# ADC.net
KiCad netlist of a schematic drawn in Altium Designer
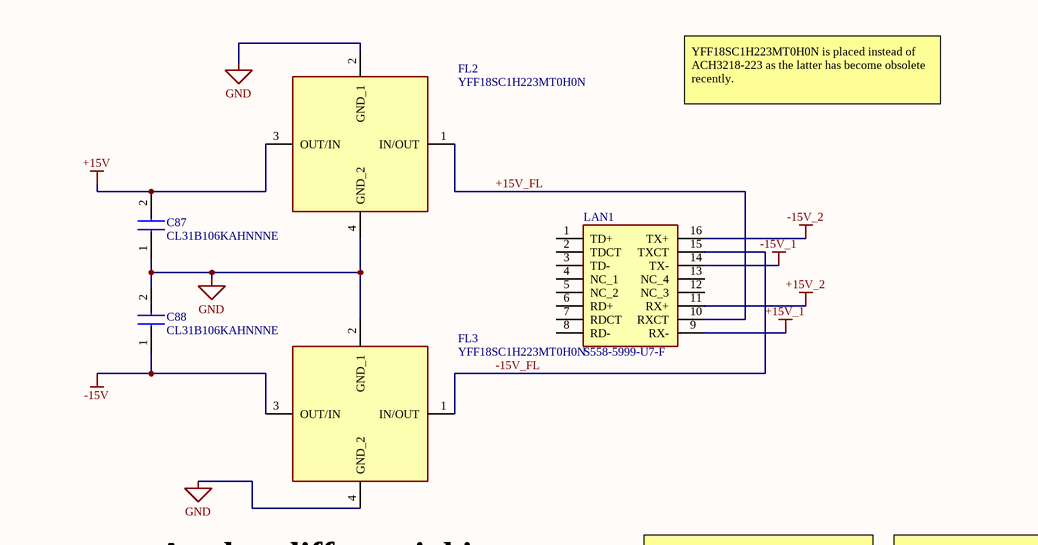
[diagram p0: ADC.SchDoc, top left]
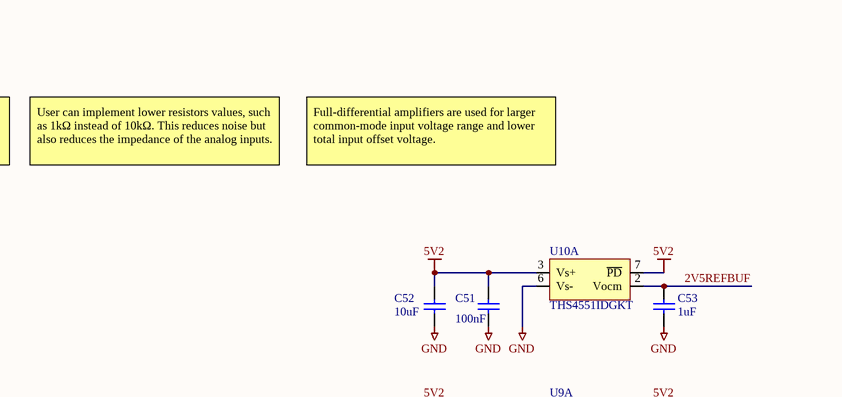
[diagram p1: ADC.SchDoc, top right]
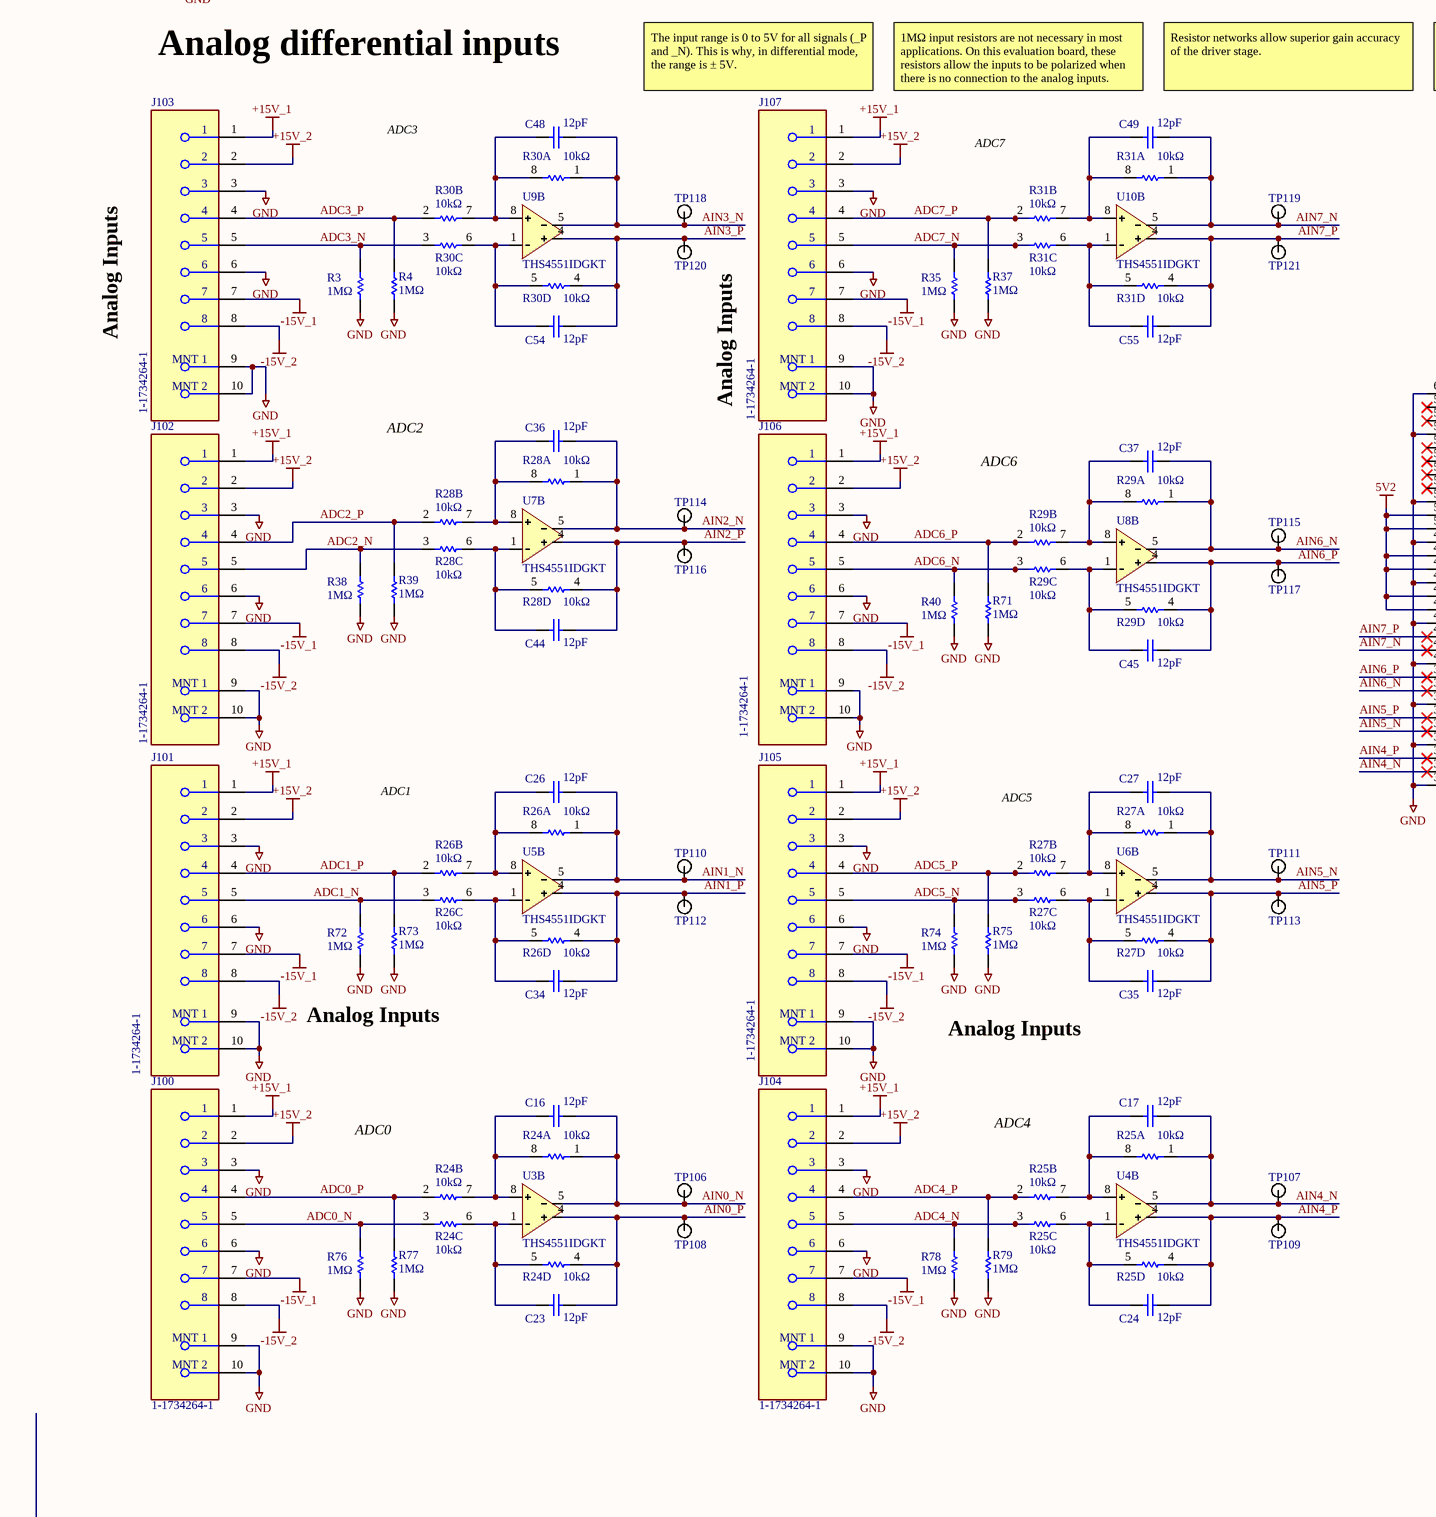
[diagram p2: ADC.SchDoc, bottom left]
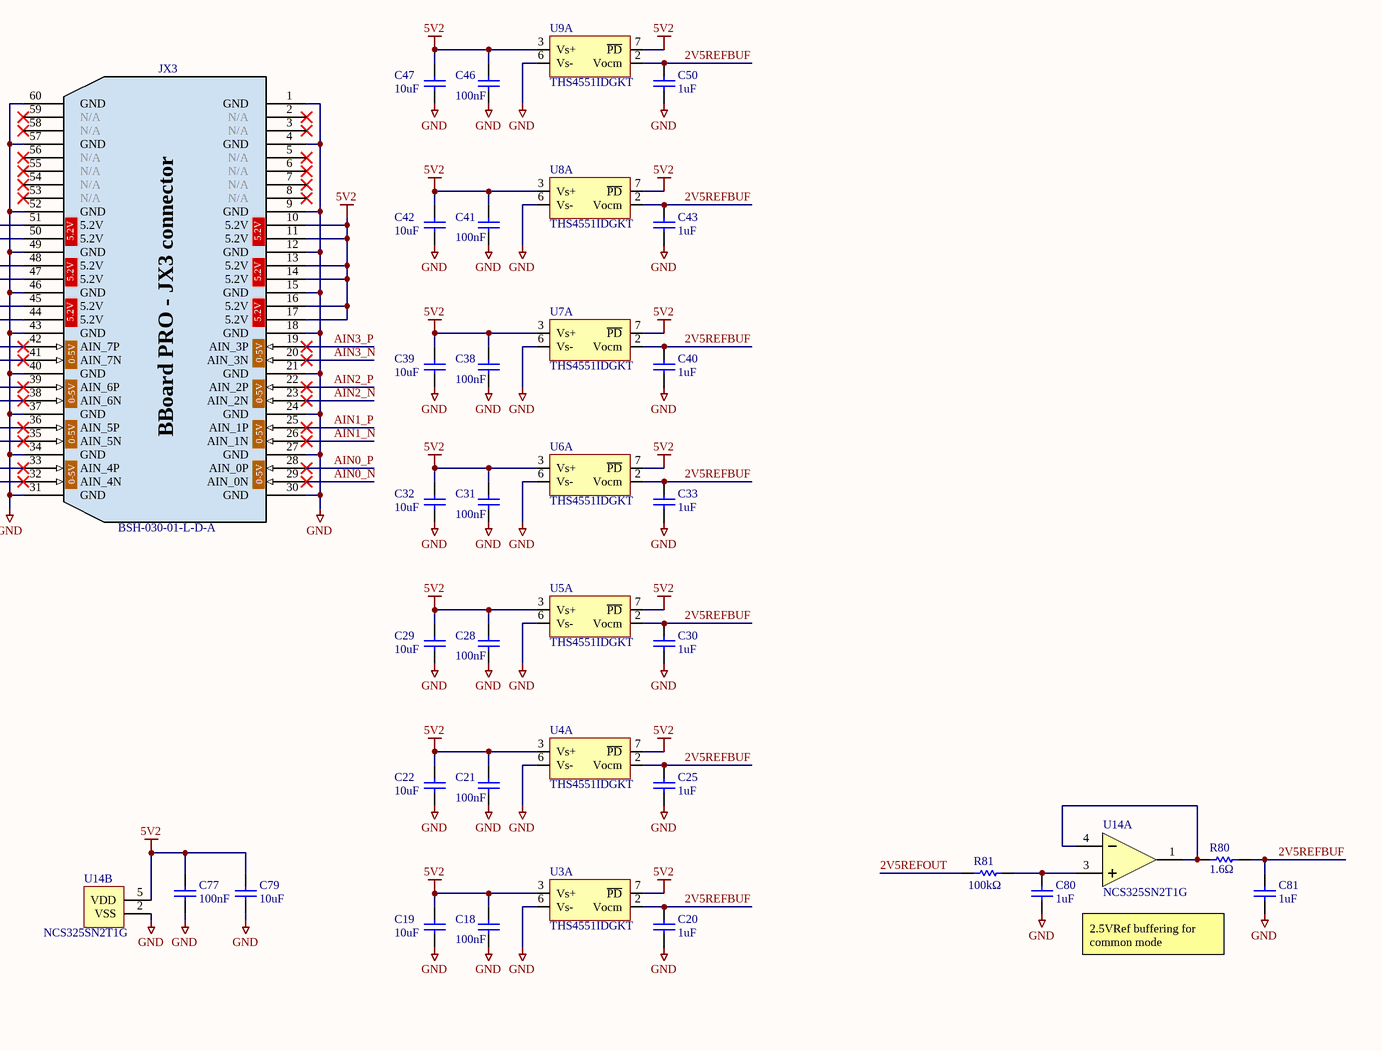
[diagram p3: ADC.SchDoc, bottom right]

(export (version "E")
  (design (tool "Eeschema 10.0.6"))
  (components
    (comp (ref "C16")
      (value "12pF")
      (footprint "CAPC1005L(0402)")
      (description "CAP CER 12PF 50V C0G 0402 5% (Generic Imperix Component)")
      (fields (field (name "TOLERANCE") "5%") (field (name "Comment") "CAP-12PF-50V-C0G-0402-5%"))
      (libsource (lib "CB3-ECB") (part "Capacitor non-polarized"))
    )
    (comp (ref "C17")
      (value "12pF")
      (footprint "CAPC1005L(0402)")
      (description "CAP CER 12PF 50V C0G 0402 5% (Generic Imperix Component)")
      (fields (field (name "TOLERANCE") "5%") (field (name "Comment") "CAP-12PF-50V-C0G-0402-5%"))
      (libsource (lib "CB3-ECB") (part "Capacitor non-polarized"))
    )
    (comp (ref "C18")
      (value "100nF")
      (footprint "CAPC1005L(0402)")
      (description "CAP CER 100NF 25V X7R 0402 10% (Generic Imperix Component)")
      (fields (field (name "TOLERANCE") "10%") (field (name "Comment") "CAP-100NF-25V-X7R-0402-10%"))
      (libsource (lib "CB3-ECB") (part "Capacitor non-polarized"))
    )
    (comp (ref "C19")
      (value "10uF")
      (footprint "CAPC1608L(0603)")
      (description "CAP CER 10UF 10V X5R 0603 10% (Generic Imperix Component)")
      (fields (field (name "TOLERANCE") "10%") (field (name "Comment") "CAP-10UF-10V-X5R-0603-10%"))
      (libsource (lib "CB3-ECB") (part "Capacitor non-polarized"))
    )
    (comp (ref "C20")
      (value "1uF")
      (footprint "CAPC1005L(0402)")
      (description "CAP CER 1UF 6.3V X5R 0402 5% (Generic Imperix Component)")
      (fields (field (name "TOLERANCE") "5%") (field (name "Comment") "CAP-1UF-6.3V-X5R-0402-5%"))
      (libsource (lib "CB3-ECB") (part "Capacitor non-polarized"))
    )
    (comp (ref "C21")
      (value "100nF")
      (footprint "CAPC1005L(0402)")
      (description "CAP CER 100NF 25V X7R 0402 10% (Generic Imperix Component)")
      (fields (field (name "TOLERANCE") "10%") (field (name "Comment") "CAP-100NF-25V-X7R-0402-10%"))
      (libsource (lib "CB3-ECB") (part "Capacitor non-polarized"))
    )
    (comp (ref "C22")
      (value "10uF")
      (footprint "CAPC1608L(0603)")
      (description "CAP CER 10UF 10V X5R 0603 10% (Generic Imperix Component)")
      (fields (field (name "TOLERANCE") "10%") (field (name "Comment") "CAP-10UF-10V-X5R-0603-10%"))
      (libsource (lib "CB3-ECB") (part "Capacitor non-polarized"))
    )
    (comp (ref "C23")
      (value "12pF")
      (footprint "CAPC1005L(0402)")
      (description "CAP CER 12PF 50V C0G 0402 5% (Generic Imperix Component)")
      (fields (field (name "TOLERANCE") "5%") (field (name "Comment") "CAP-12PF-50V-C0G-0402-5%"))
      (libsource (lib "CB3-ECB") (part "Capacitor non-polarized"))
    )
    (comp (ref "C24")
      (value "12pF")
      (footprint "CAPC1005L(0402)")
      (description "CAP CER 12PF 50V C0G 0402 5% (Generic Imperix Component)")
      (fields (field (name "TOLERANCE") "5%") (field (name "Comment") "CAP-12PF-50V-C0G-0402-5%"))
      (libsource (lib "CB3-ECB") (part "Capacitor non-polarized"))
    )
    (comp (ref "C25")
      (value "1uF")
      (footprint "CAPC1005L(0402)")
      (description "CAP CER 1UF 6.3V X5R 0402 5% (Generic Imperix Component)")
      (fields (field (name "TOLERANCE") "5%") (field (name "Comment") "CAP-1UF-6.3V-X5R-0402-5%"))
      (libsource (lib "CB3-ECB") (part "Capacitor non-polarized"))
    )
    (comp (ref "C26")
      (value "12pF")
      (footprint "CAPC1005L(0402)")
      (description "CAP CER 12PF 50V C0G 0402 5% (Generic Imperix Component)")
      (fields (field (name "TOLERANCE") "5%") (field (name "Comment") "CAP-12PF-50V-C0G-0402-5%"))
      (libsource (lib "CB3-ECB") (part "Capacitor non-polarized"))
    )
    (comp (ref "C27")
      (value "12pF")
      (footprint "CAPC1005L(0402)")
      (description "CAP CER 12PF 50V C0G 0402 5% (Generic Imperix Component)")
      (fields (field (name "TOLERANCE") "5%") (field (name "Comment") "CAP-12PF-50V-C0G-0402-5%"))
      (libsource (lib "CB3-ECB") (part "Capacitor non-polarized"))
    )
    (comp (ref "C28")
      (value "100nF")
      (footprint "CAPC1005L(0402)")
      (description "CAP CER 100NF 25V X7R 0402 10% (Generic Imperix Component)")
      (fields (field (name "TOLERANCE") "10%") (field (name "Comment") "CAP-100NF-25V-X7R-0402-10%"))
      (libsource (lib "CB3-ECB") (part "Capacitor non-polarized"))
    )
    (comp (ref "C29")
      (value "10uF")
      (footprint "CAPC1608L(0603)")
      (description "CAP CER 10UF 10V X5R 0603 10% (Generic Imperix Component)")
      (fields (field (name "TOLERANCE") "10%") (field (name "Comment") "CAP-10UF-10V-X5R-0603-10%"))
      (libsource (lib "CB3-ECB") (part "Capacitor non-polarized"))
    )
    (comp (ref "C30")
      (value "1uF")
      (footprint "CAPC1005L(0402)")
      (description "CAP CER 1UF 6.3V X5R 0402 5% (Generic Imperix Component)")
      (fields (field (name "TOLERANCE") "5%") (field (name "Comment") "CAP-1UF-6.3V-X5R-0402-5%"))
      (libsource (lib "CB3-ECB") (part "Capacitor non-polarized"))
    )
    (comp (ref "C31")
      (value "100nF")
      (footprint "CAPC1005L(0402)")
      (description "CAP CER 100NF 25V X7R 0402 10% (Generic Imperix Component)")
      (fields (field (name "TOLERANCE") "10%") (field (name "Comment") "CAP-100NF-25V-X7R-0402-10%"))
      (libsource (lib "CB3-ECB") (part "Capacitor non-polarized"))
    )
    (comp (ref "C32")
      (value "10uF")
      (footprint "CAPC1608L(0603)")
      (description "CAP CER 10UF 10V X5R 0603 10% (Generic Imperix Component)")
      (fields (field (name "TOLERANCE") "10%") (field (name "Comment") "CAP-10UF-10V-X5R-0603-10%"))
      (libsource (lib "CB3-ECB") (part "Capacitor non-polarized"))
    )
    (comp (ref "C33")
      (value "1uF")
      (footprint "CAPC1005L(0402)")
      (description "CAP CER 1UF 6.3V X5R 0402 5% (Generic Imperix Component)")
      (fields (field (name "TOLERANCE") "5%") (field (name "Comment") "CAP-1UF-6.3V-X5R-0402-5%"))
      (libsource (lib "CB3-ECB") (part "Capacitor non-polarized"))
    )
    (comp (ref "C34")
      (value "12pF")
      (footprint "CAPC1005L(0402)")
      (description "CAP CER 12PF 50V C0G 0402 5% (Generic Imperix Component)")
      (fields (field (name "TOLERANCE") "5%") (field (name "Comment") "CAP-12PF-50V-C0G-0402-5%"))
      (libsource (lib "CB3-ECB") (part "Capacitor non-polarized"))
    )
    (comp (ref "C35")
      (value "12pF")
      (footprint "CAPC1005L(0402)")
      (description "CAP CER 12PF 50V C0G 0402 5% (Generic Imperix Component)")
      (fields (field (name "TOLERANCE") "5%") (field (name "Comment") "CAP-12PF-50V-C0G-0402-5%"))
      (libsource (lib "CB3-ECB") (part "Capacitor non-polarized"))
    )
    (comp (ref "C36")
      (value "12pF")
      (footprint "CAPC1005L(0402)")
      (description "CAP CER 12PF 50V C0G 0402 5% (Generic Imperix Component)")
      (fields (field (name "TOLERANCE") "5%") (field (name "Comment") "CAP-12PF-50V-C0G-0402-5%"))
      (libsource (lib "CB3-ECB") (part "Capacitor non-polarized"))
    )
    (comp (ref "C37")
      (value "12pF")
      (footprint "CAPC1005L(0402)")
      (description "CAP CER 12PF 50V C0G 0402 5% (Generic Imperix Component)")
      (fields (field (name "TOLERANCE") "5%") (field (name "Comment") "CAP-12PF-50V-C0G-0402-5%"))
      (libsource (lib "CB3-ECB") (part "Capacitor non-polarized"))
    )
    (comp (ref "C38")
      (value "100nF")
      (footprint "CAPC1005L(0402)")
      (description "CAP CER 100NF 25V X7R 0402 10% (Generic Imperix Component)")
      (fields (field (name "TOLERANCE") "10%") (field (name "Comment") "CAP-100NF-25V-X7R-0402-10%"))
      (libsource (lib "CB3-ECB") (part "Capacitor non-polarized"))
    )
    (comp (ref "C39")
      (value "10uF")
      (footprint "CAPC1608L(0603)")
      (description "CAP CER 10UF 10V X5R 0603 10% (Generic Imperix Component)")
      (fields (field (name "TOLERANCE") "10%") (field (name "Comment") "CAP-10UF-10V-X5R-0603-10%"))
      (libsource (lib "CB3-ECB") (part "Capacitor non-polarized"))
    )
    (comp (ref "C40")
      (value "1uF")
      (footprint "CAPC1005L(0402)")
      (description "CAP CER 1UF 6.3V X5R 0402 5% (Generic Imperix Component)")
      (fields (field (name "TOLERANCE") "5%") (field (name "Comment") "CAP-1UF-6.3V-X5R-0402-5%"))
      (libsource (lib "CB3-ECB") (part "Capacitor non-polarized"))
    )
    (comp (ref "C41")
      (value "100nF")
      (footprint "CAPC1005L(0402)")
      (description "CAP CER 100NF 25V X7R 0402 10% (Generic Imperix Component)")
      (fields (field (name "TOLERANCE") "10%") (field (name "Comment") "CAP-100NF-25V-X7R-0402-10%"))
      (libsource (lib "CB3-ECB") (part "Capacitor non-polarized"))
    )
    (comp (ref "C42")
      (value "10uF")
      (footprint "CAPC1608L(0603)")
      (description "CAP CER 10UF 10V X5R 0603 10% (Generic Imperix Component)")
      (fields (field (name "TOLERANCE") "10%") (field (name "Comment") "CAP-10UF-10V-X5R-0603-10%"))
      (libsource (lib "CB3-ECB") (part "Capacitor non-polarized"))
    )
    (comp (ref "C43")
      (value "1uF")
      (footprint "CAPC1005L(0402)")
      (description "CAP CER 1UF 6.3V X5R 0402 5% (Generic Imperix Component)")
      (fields (field (name "TOLERANCE") "5%") (field (name "Comment") "CAP-1UF-6.3V-X5R-0402-5%"))
      (libsource (lib "CB3-ECB") (part "Capacitor non-polarized"))
    )
    (comp (ref "C44")
      (value "12pF")
      (footprint "CAPC1005L(0402)")
      (description "CAP CER 12PF 50V C0G 0402 5% (Generic Imperix Component)")
      (fields (field (name "TOLERANCE") "5%") (field (name "Comment") "CAP-12PF-50V-C0G-0402-5%"))
      (libsource (lib "CB3-ECB") (part "Capacitor non-polarized"))
    )
    (comp (ref "C45")
      (value "12pF")
      (footprint "CAPC1005L(0402)")
      (description "CAP CER 12PF 50V C0G 0402 5% (Generic Imperix Component)")
      (fields (field (name "TOLERANCE") "5%") (field (name "Comment") "CAP-12PF-50V-C0G-0402-5%"))
      (libsource (lib "CB3-ECB") (part "Capacitor non-polarized"))
    )
    (comp (ref "C46")
      (value "100nF")
      (footprint "CAPC1005L(0402)")
      (description "CAP CER 100NF 25V X7R 0402 10% (Generic Imperix Component)")
      (fields (field (name "TOLERANCE") "10%") (field (name "Comment") "CAP-100NF-25V-X7R-0402-10%"))
      (libsource (lib "CB3-ECB") (part "Capacitor non-polarized"))
    )
    (comp (ref "C47")
      (value "10uF")
      (footprint "CAPC1608L(0603)")
      (description "CAP CER 10UF 10V X5R 0603 10% (Generic Imperix Component)")
      (fields (field (name "TOLERANCE") "10%") (field (name "Comment") "CAP-10UF-10V-X5R-0603-10%"))
      (libsource (lib "CB3-ECB") (part "Capacitor non-polarized"))
    )
    (comp (ref "C48")
      (value "12pF")
      (footprint "CAPC1005L(0402)")
      (description "CAP CER 12PF 50V C0G 0402 5% (Generic Imperix Component)")
      (fields (field (name "TOLERANCE") "5%") (field (name "Comment") "CAP-12PF-50V-C0G-0402-5%"))
      (libsource (lib "CB3-ECB") (part "Capacitor non-polarized"))
    )
    (comp (ref "C49")
      (value "12pF")
      (footprint "CAPC1005L(0402)")
      (description "CAP CER 12PF 50V C0G 0402 5% (Generic Imperix Component)")
      (fields (field (name "TOLERANCE") "5%") (field (name "Comment") "CAP-12PF-50V-C0G-0402-5%"))
      (libsource (lib "CB3-ECB") (part "Capacitor non-polarized"))
    )
    (comp (ref "C50")
      (value "1uF")
      (footprint "CAPC1005L(0402)")
      (description "CAP CER 1UF 6.3V X5R 0402 5% (Generic Imperix Component)")
      (fields (field (name "TOLERANCE") "5%") (field (name "Comment") "CAP-1UF-6.3V-X5R-0402-5%"))
      (libsource (lib "CB3-ECB") (part "Capacitor non-polarized"))
    )
    (comp (ref "C51")
      (value "100nF")
      (footprint "CAPC1005L(0402)")
      (description "CAP CER 100NF 25V X7R 0402 10% (Generic Imperix Component)")
      (fields (field (name "TOLERANCE") "10%") (field (name "Comment") "CAP-100NF-25V-X7R-0402-10%"))
      (libsource (lib "CB3-ECB") (part "Capacitor non-polarized"))
    )
    (comp (ref "C52")
      (value "10uF")
      (footprint "CAPC1608L(0603)")
      (description "CAP CER 10UF 10V X5R 0603 10% (Generic Imperix Component)")
      (fields (field (name "TOLERANCE") "10%") (field (name "Comment") "CAP-10UF-10V-X5R-0603-10%"))
      (libsource (lib "CB3-ECB") (part "Capacitor non-polarized"))
    )
    (comp (ref "C53")
      (value "1uF")
      (footprint "CAPC1005L(0402)")
      (description "CAP CER 1UF 6.3V X5R 0402 5% (Generic Imperix Component)")
      (fields (field (name "TOLERANCE") "5%") (field (name "Comment") "CAP-1UF-6.3V-X5R-0402-5%"))
      (libsource (lib "CB3-ECB") (part "Capacitor non-polarized"))
    )
    (comp (ref "C54")
      (value "12pF")
      (footprint "CAPC1005L(0402)")
      (description "CAP CER 12PF 50V C0G 0402 5% (Generic Imperix Component)")
      (fields (field (name "TOLERANCE") "5%") (field (name "Comment") "CAP-12PF-50V-C0G-0402-5%"))
      (libsource (lib "CB3-ECB") (part "Capacitor non-polarized"))
    )
    (comp (ref "C55")
      (value "12pF")
      (footprint "CAPC1005L(0402)")
      (description "CAP CER 12PF 50V C0G 0402 5% (Generic Imperix Component)")
      (fields (field (name "TOLERANCE") "5%") (field (name "Comment") "CAP-12PF-50V-C0G-0402-5%"))
      (libsource (lib "CB3-ECB") (part "Capacitor non-polarized"))
    )
    (comp (ref "C77")
      (value "100nF")
      (footprint "CAPC1005L(0402)")
      (description "CAP CER 100NF 25V X7R 0402 10% (Generic Imperix Component)")
      (fields (field (name "TOLERANCE") "10%") (field (name "Comment") "CAP-100NF-25V-X7R-0402-10%"))
      (libsource (lib "CB3-ECB") (part "Capacitor non-polarized"))
    )
    (comp (ref "C79")
      (value "10uF")
      (footprint "CAPC1608L(0603)")
      (description "CAP CER 10UF 10V X5R 0603 10% (Generic Imperix Component)")
      (fields (field (name "TOLERANCE") "10%") (field (name "Comment") "CAP-10UF-10V-X5R-0603-10%"))
      (libsource (lib "CB3-ECB") (part "Capacitor non-polarized"))
    )
    (comp (ref "C80")
      (value "1uF")
      (footprint "CAPC1005L(0402)")
      (description "CAP CER 1UF 6.3V X5R 0402 5% (Generic Imperix Component)")
      (fields (field (name "TOLERANCE") "5%") (field (name "Comment") "CAP-1UF-6.3V-X5R-0402-5%"))
      (libsource (lib "CB3-ECB") (part "Capacitor non-polarized"))
    )
    (comp (ref "C81")
      (value "1uF")
      (footprint "CAPC1005L(0402)")
      (description "CAP CER 1UF 6.3V X5R 0402 5% (Generic Imperix Component)")
      (fields (field (name "TOLERANCE") "5%") (field (name "Comment") "CAP-1UF-6.3V-X5R-0402-5%"))
      (libsource (lib "CB3-ECB") (part "Capacitor non-polarized"))
    )
    (comp (ref "C87")
      (value "CL31B106KAHNNNE")
      (footprint "SamacSys:CAPC3216X180N")
      (description "Capacitor")
      (fields (field (name "MOUSER PART NUMBER") "187-CL31B106KAHNNNE"))
      (libsource (lib "SamacSys") (part "CL31B106KAHNNNE"))
    )
    (comp (ref "C88")
      (value "CL31B106KAHNNNE")
      (footprint "SamacSys:CAPC3216X180N")
      (description "Capacitor")
      (fields (field (name "MOUSER PART NUMBER") "187-CL31B106KAHNNNE"))
      (libsource (lib "SamacSys") (part "CL31B106KAHNNNE"))
    )
    (comp (ref "FL2")
      (value "YFF18SC1H223MT0H0N")
      (footprint "SamacSys:YFF18SC1H223MT0H0N")
      (description "Filter")
      (fields (field (name "MOUSER PART NUMBER") "810-YFF18SC1H223MTHN"))
      (libsource (lib "*") (part "YFF18SC1H223MT0H0N"))
    )
    (comp (ref "FL3")
      (value "YFF18SC1H223MT0H0N")
      (footprint "SamacSys:YFF18SC1H223MT0H0N")
      (description "Filter")
      (fields (field (name "MOUSER PART NUMBER") "810-YFF18SC1H223MTHN"))
      (libsource (lib "*") (part "YFF18SC1H223MT0H0N"))
    )
    (comp (ref "J100")
      (value "1-1734264-1")
      (footprint "FP-1-1734264-1-MFG")
      (description "1-1734264-1 Conn Modular Jack F 8 POS 1.02mm Solder RA Thru-Hole 8 Terminal 1 Port Cat 5 Box/Tray")
      (libsource (lib "Altium Content Vault") (part "cba65c9947a6637759d8dec63cb3c15"))
    )
    (comp (ref "J101")
      (value "1-1734264-1")
      (footprint "FP-1-1734264-1-MFG")
      (description "1-1734264-1 Conn Modular Jack F 8 POS 1.02mm Solder RA Thru-Hole 8 Terminal 1 Port Cat 5 Box/Tray")
      (libsource (lib "Altium Content Vault") (part "cba65c9947a6637759d8dec63cb3c15"))
    )
    (comp (ref "J102")
      (value "1-1734264-1")
      (footprint "FP-1-1734264-1-MFG")
      (description "1-1734264-1 Conn Modular Jack F 8 POS 1.02mm Solder RA Thru-Hole 8 Terminal 1 Port Cat 5 Box/Tray")
      (libsource (lib "Altium Content Vault") (part "cba65c9947a6637759d8dec63cb3c15"))
    )
    (comp (ref "J103")
      (value "1-1734264-1")
      (footprint "FP-1-1734264-1-MFG")
      (description "1-1734264-1 Conn Modular Jack F 8 POS 1.02mm Solder RA Thru-Hole 8 Terminal 1 Port Cat 5 Box/Tray")
      (libsource (lib "Altium Content Vault") (part "cba65c9947a6637759d8dec63cb3c15"))
    )
    (comp (ref "J104")
      (value "1-1734264-1")
      (footprint "FP-1-1734264-1-MFG")
      (description "1-1734264-1 Conn Modular Jack F 8 POS 1.02mm Solder RA Thru-Hole 8 Terminal 1 Port Cat 5 Box/Tray")
      (libsource (lib "Altium Content Vault") (part "cba65c9947a6637759d8dec63cb3c15"))
    )
    (comp (ref "J105")
      (value "1-1734264-1")
      (footprint "FP-1-1734264-1-MFG")
      (description "1-1734264-1 Conn Modular Jack F 8 POS 1.02mm Solder RA Thru-Hole 8 Terminal 1 Port Cat 5 Box/Tray")
      (libsource (lib "Altium Content Vault") (part "cba65c9947a6637759d8dec63cb3c15"))
    )
    (comp (ref "J106")
      (value "1-1734264-1")
      (footprint "FP-1-1734264-1-MFG")
      (description "1-1734264-1 Conn Modular Jack F 8 POS 1.02mm Solder RA Thru-Hole 8 Terminal 1 Port Cat 5 Box/Tray")
      (libsource (lib "Altium Content Vault") (part "cba65c9947a6637759d8dec63cb3c15"))
    )
    (comp (ref "J107")
      (value "1-1734264-1")
      (footprint "FP-1-1734264-1-MFG")
      (description "1-1734264-1 Conn Modular Jack F 8 POS 1.02mm Solder RA Thru-Hole 8 Terminal 1 Port Cat 5 Box/Tray")
      (libsource (lib "Altium Content Vault") (part "cba65c9947a6637759d8dec63cb3c15"))
    )
    (comp (ref "JX3")
      (value "BSH-030-01-L-D-A")
      (footprint "BSH-030-01-L-D-A")
      (description "JX3 for BBoard")
      (libsource (lib "CB3-ECB") (part "JX3 for BBoard"))
    )
    (comp (ref "LAN1")
      (value "S558-5999-U7-F")
      (footprint "SamacSys:SOIC127P920X571-16N")
      (description "Integrated Circuit")
      (fields (field (name "MOUSER PART NUMBER") "530-S558-5999-U7-F"))
      (libsource (lib "SamacSys") (part "S558-5999-U7-F"))
    )
    (comp (ref "R3")
      (value "1MΩ")
      (footprint "RESC1005L(0402)")
      (description "RES SMD 1MΩ 1/16W 100PPM 0402 1% (Generic Imperix Component)")
      (fields (field (name "TOLERANCE") "1%") (field (name "Comment") "RES-1MΩ-1/16W-100PPM-0402-1%"))
      (libsource (lib "CB3-ECB") (part "Resistor"))
    )
    (comp (ref "R4")
      (value "1MΩ")
      (footprint "RESC1005L(0402)")
      (description "RES SMD 1MΩ 1/16W 100PPM 0402 1% (Generic Imperix Component)")
      (fields (field (name "TOLERANCE") "1%") (field (name "Comment") "RES-1MΩ-1/16W-100PPM-0402-1%"))
      (libsource (lib "CB3-ECB") (part "Resistor"))
    )
    (comp (ref "R24")
      (value "10kΩ")
      (footprint "RESQUAD1206")
      (fields (field (name "TOLERANCE") "0.1%") (field (name "Comment") "ACASA1002S1002P100"))
      (libsource (lib "CB3-ECB") (part "Resistor Array Quad"))
    )
    (comp (ref "R25")
      (value "10kΩ")
      (footprint "RESQUAD1206")
      (fields (field (name "TOLERANCE") "0.1%") (field (name "Comment") "ACASA1002S1002P100"))
      (libsource (lib "CB3-ECB") (part "Resistor Array Quad"))
    )
    (comp (ref "R26")
      (value "10kΩ")
      (footprint "RESQUAD1206")
      (fields (field (name "TOLERANCE") "0.1%") (field (name "Comment") "ACASA1002S1002P100"))
      (libsource (lib "CB3-ECB") (part "Resistor Array Quad"))
    )
    (comp (ref "R27")
      (value "10kΩ")
      (footprint "RESQUAD1206")
      (fields (field (name "TOLERANCE") "0.1%") (field (name "Comment") "ACASA1002S1002P100"))
      (libsource (lib "CB3-ECB") (part "Resistor Array Quad"))
    )
    (comp (ref "R28")
      (value "10kΩ")
      (footprint "RESQUAD1206")
      (fields (field (name "TOLERANCE") "0.1%") (field (name "Comment") "ACASA1002S1002P100"))
      (libsource (lib "CB3-ECB") (part "Resistor Array Quad"))
    )
    (comp (ref "R29")
      (value "10kΩ")
      (footprint "RESQUAD1206")
      (fields (field (name "TOLERANCE") "0.1%") (field (name "Comment") "ACASA1002S1002P100"))
      (libsource (lib "CB3-ECB") (part "Resistor Array Quad"))
    )
    (comp (ref "R30")
      (value "10kΩ")
      (footprint "RESQUAD1206")
      (fields (field (name "TOLERANCE") "0.1%") (field (name "Comment") "ACASA1002S1002P100"))
      (libsource (lib "CB3-ECB") (part "Resistor Array Quad"))
    )
    (comp (ref "R31")
      (value "10kΩ")
      (footprint "RESQUAD1206")
      (fields (field (name "TOLERANCE") "0.1%") (field (name "Comment") "ACASA1002S1002P100"))
      (libsource (lib "CB3-ECB") (part "Resistor Array Quad"))
    )
    (comp (ref "R35")
      (value "1MΩ")
      (footprint "RESC1005L(0402)")
      (description "RES SMD 1MΩ 1/16W 100PPM 0402 1% (Generic Imperix Component)")
      (fields (field (name "TOLERANCE") "1%") (field (name "Comment") "RES-1MΩ-1/16W-100PPM-0402-1%"))
      (libsource (lib "CB3-ECB") (part "Resistor"))
    )
    (comp (ref "R37")
      (value "1MΩ")
      (footprint "RESC1005L(0402)")
      (description "RES SMD 1MΩ 1/16W 100PPM 0402 1% (Generic Imperix Component)")
      (fields (field (name "TOLERANCE") "1%") (field (name "Comment") "RES-1MΩ-1/16W-100PPM-0402-1%"))
      (libsource (lib "CB3-ECB") (part "Resistor"))
    )
    (comp (ref "R38")
      (value "1MΩ")
      (footprint "RESC1005L(0402)")
      (description "RES SMD 1MΩ 1/16W 100PPM 0402 1% (Generic Imperix Component)")
      (fields (field (name "TOLERANCE") "1%") (field (name "Comment") "RES-1MΩ-1/16W-100PPM-0402-1%"))
      (libsource (lib "CB3-ECB") (part "Resistor"))
    )
    (comp (ref "R39")
      (value "1MΩ")
      (footprint "RESC1005L(0402)")
      (description "RES SMD 1MΩ 1/16W 100PPM 0402 1% (Generic Imperix Component)")
      (fields (field (name "TOLERANCE") "1%") (field (name "Comment") "RES-1MΩ-1/16W-100PPM-0402-1%"))
      (libsource (lib "CB3-ECB") (part "Resistor"))
    )
    (comp (ref "R40")
      (value "1MΩ")
      (footprint "RESC1005L(0402)")
      (description "RES SMD 1MΩ 1/16W 100PPM 0402 1% (Generic Imperix Component)")
      (fields (field (name "TOLERANCE") "1%") (field (name "Comment") "RES-1MΩ-1/16W-100PPM-0402-1%"))
      (libsource (lib "CB3-ECB") (part "Resistor"))
    )
    (comp (ref "R71")
      (value "1MΩ")
      (footprint "RESC1005L(0402)")
      (description "RES SMD 1MΩ 1/16W 100PPM 0402 1% (Generic Imperix Component)")
      (fields (field (name "TOLERANCE") "1%") (field (name "Comment") "RES-1MΩ-1/16W-100PPM-0402-1%"))
      (libsource (lib "CB3-ECB") (part "Resistor"))
    )
    (comp (ref "R72")
      (value "1MΩ")
      (footprint "RESC1005L(0402)")
      (description "RES SMD 1MΩ 1/16W 100PPM 0402 1% (Generic Imperix Component)")
      (fields (field (name "TOLERANCE") "1%") (field (name "Comment") "RES-1MΩ-1/16W-100PPM-0402-1%"))
      (libsource (lib "CB3-ECB") (part "Resistor"))
    )
    (comp (ref "R73")
      (value "1MΩ")
      (footprint "RESC1005L(0402)")
      (description "RES SMD 1MΩ 1/16W 100PPM 0402 1% (Generic Imperix Component)")
      (fields (field (name "TOLERANCE") "1%") (field (name "Comment") "RES-1MΩ-1/16W-100PPM-0402-1%"))
      (libsource (lib "CB3-ECB") (part "Resistor"))
    )
    (comp (ref "R74")
      (value "1MΩ")
      (footprint "RESC1005L(0402)")
      (description "RES SMD 1MΩ 1/16W 100PPM 0402 1% (Generic Imperix Component)")
      (fields (field (name "TOLERANCE") "1%") (field (name "Comment") "RES-1MΩ-1/16W-100PPM-0402-1%"))
      (libsource (lib "CB3-ECB") (part "Resistor"))
    )
    (comp (ref "R75")
      (value "1MΩ")
      (footprint "RESC1005L(0402)")
      (description "RES SMD 1MΩ 1/16W 100PPM 0402 1% (Generic Imperix Component)")
      (fields (field (name "TOLERANCE") "1%") (field (name "Comment") "RES-1MΩ-1/16W-100PPM-0402-1%"))
      (libsource (lib "CB3-ECB") (part "Resistor"))
    )
    (comp (ref "R76")
      (value "1MΩ")
      (footprint "RESC1005L(0402)")
      (description "RES SMD 1MΩ 1/16W 100PPM 0402 1% (Generic Imperix Component)")
      (fields (field (name "TOLERANCE") "1%") (field (name "Comment") "RES-1MΩ-1/16W-100PPM-0402-1%"))
      (libsource (lib "CB3-ECB") (part "Resistor"))
    )
    (comp (ref "R77")
      (value "1MΩ")
      (footprint "RESC1005L(0402)")
      (description "RES SMD 1MΩ 1/16W 100PPM 0402 1% (Generic Imperix Component)")
      (fields (field (name "TOLERANCE") "1%") (field (name "Comment") "RES-1MΩ-1/16W-100PPM-0402-1%"))
      (libsource (lib "CB3-ECB") (part "Resistor"))
    )
    (comp (ref "R78")
      (value "1MΩ")
      (footprint "RESC1005L(0402)")
      (description "RES SMD 1MΩ 1/16W 100PPM 0402 1% (Generic Imperix Component)")
      (fields (field (name "TOLERANCE") "1%") (field (name "Comment") "RES-1MΩ-1/16W-100PPM-0402-1%"))
      (libsource (lib "CB3-ECB") (part "Resistor"))
    )
    (comp (ref "R79")
      (value "1MΩ")
      (footprint "RESC1005L(0402)")
      (description "RES SMD 1MΩ 1/16W 100PPM 0402 1% (Generic Imperix Component)")
      (fields (field (name "TOLERANCE") "1%") (field (name "Comment") "RES-1MΩ-1/16W-100PPM-0402-1%"))
      (libsource (lib "CB3-ECB") (part "Resistor"))
    )
    (comp (ref "R80")
      (value "1.6Ω")
      (footprint "RESC1005L(0402)")
      (description "RES SMD 1.6Ω 1/16WW 200PPM 0402 5% (Generic Imperix Component)")
      (fields (field (name "TOLERANCE") "5%") (field (name "Comment") "RES-1.6Ω-1/16WW-200PPM-0402-5%"))
      (libsource (lib "CB3-ECB") (part "Resistor"))
    )
    (comp (ref "R81")
      (value "100kΩ")
      (footprint "RESC1005L(0402)")
      (description "RES SMD 100KΩ 1/16W 100PPM 0402 1% (Generic Imperix Component)")
      (fields (field (name "TOLERANCE") "1%") (field (name "Comment") "RES-100KΩ-1/16W-100PPM-0402-1%"))
      (libsource (lib "CB3-ECB") (part "Resistor"))
    )
    (comp (ref "TP106")
      (value "5001")
      (footprint "5001")
      (description "Black PC Test Point, Miniature Phosphor Bronze Silver Plating Through Hole Mounting Type")
      (libsource (lib "CB3-ECB") (part "Testpoint"))
    )
    (comp (ref "TP107")
      (value "5001")
      (footprint "5001")
      (description "Black PC Test Point, Miniature Phosphor Bronze Silver Plating Through Hole Mounting Type")
      (libsource (lib "CB3-ECB") (part "Testpoint"))
    )
    (comp (ref "TP108")
      (value "5001")
      (footprint "5001")
      (description "Black PC Test Point, Miniature Phosphor Bronze Silver Plating Through Hole Mounting Type")
      (libsource (lib "CB3-ECB") (part "Testpoint"))
    )
    (comp (ref "TP109")
      (value "5001")
      (footprint "5001")
      (description "Black PC Test Point, Miniature Phosphor Bronze Silver Plating Through Hole Mounting Type")
      (libsource (lib "CB3-ECB") (part "Testpoint"))
    )
    (comp (ref "TP110")
      (value "5001")
      (footprint "5001")
      (description "Black PC Test Point, Miniature Phosphor Bronze Silver Plating Through Hole Mounting Type")
      (libsource (lib "CB3-ECB") (part "Testpoint"))
    )
    (comp (ref "TP111")
      (value "5001")
      (footprint "5001")
      (description "Black PC Test Point, Miniature Phosphor Bronze Silver Plating Through Hole Mounting Type")
      (libsource (lib "CB3-ECB") (part "Testpoint"))
    )
    (comp (ref "TP112")
      (value "5001")
      (footprint "5001")
      (description "Black PC Test Point, Miniature Phosphor Bronze Silver Plating Through Hole Mounting Type")
      (libsource (lib "CB3-ECB") (part "Testpoint"))
    )
    (comp (ref "TP113")
      (value "5001")
      (footprint "5001")
      (description "Black PC Test Point, Miniature Phosphor Bronze Silver Plating Through Hole Mounting Type")
      (libsource (lib "CB3-ECB") (part "Testpoint"))
    )
    (comp (ref "TP114")
      (value "5001")
      (footprint "5001")
      (description "Black PC Test Point, Miniature Phosphor Bronze Silver Plating Through Hole Mounting Type")
      (libsource (lib "CB3-ECB") (part "Testpoint"))
    )
    (comp (ref "TP115")
      (value "5001")
      (footprint "5001")
      (description "Black PC Test Point, Miniature Phosphor Bronze Silver Plating Through Hole Mounting Type")
      (libsource (lib "CB3-ECB") (part "Testpoint"))
    )
    (comp (ref "TP116")
      (value "5001")
      (footprint "5001")
      (description "Black PC Test Point, Miniature Phosphor Bronze Silver Plating Through Hole Mounting Type")
      (libsource (lib "CB3-ECB") (part "Testpoint"))
    )
    (comp (ref "TP117")
      (value "5001")
      (footprint "5001")
      (description "Black PC Test Point, Miniature Phosphor Bronze Silver Plating Through Hole Mounting Type")
      (libsource (lib "CB3-ECB") (part "Testpoint"))
    )
    (comp (ref "TP118")
      (value "5001")
      (footprint "5001")
      (description "Black PC Test Point, Miniature Phosphor Bronze Silver Plating Through Hole Mounting Type")
      (libsource (lib "CB3-ECB") (part "Testpoint"))
    )
    (comp (ref "TP119")
      (value "5001")
      (footprint "5001")
      (description "Black PC Test Point, Miniature Phosphor Bronze Silver Plating Through Hole Mounting Type")
      (libsource (lib "CB3-ECB") (part "Testpoint"))
    )
    (comp (ref "TP120")
      (value "5001")
      (footprint "5001")
      (description "Black PC Test Point, Miniature Phosphor Bronze Silver Plating Through Hole Mounting Type")
      (libsource (lib "CB3-ECB") (part "Testpoint"))
    )
    (comp (ref "TP121")
      (value "5001")
      (footprint "5001")
      (description "Black PC Test Point, Miniature Phosphor Bronze Silver Plating Through Hole Mounting Type")
      (libsource (lib "CB3-ECB") (part "Testpoint"))
    )
    (comp (ref "U3")
      (value "THS4551IDGKT")
      (footprint "TSOP65P490-8AL")
      (description "Low Noise, Precision, 150MHz, Fully Differential Amplifier 8-TSOP -40 to 125")
      (libsource (lib "CB3-ECB") (part "THS4551IDGKT"))
    )
    (comp (ref "U4")
      (value "THS4551IDGKT")
      (footprint "TSOP65P490-8AL")
      (description "Low Noise, Precision, 150MHz, Fully Differential Amplifier 8-TSOP -40 to 125")
      (libsource (lib "CB3-ECB") (part "THS4551IDGKT"))
    )
    (comp (ref "U5")
      (value "THS4551IDGKT")
      (footprint "TSOP65P490-8AL")
      (description "Low Noise, Precision, 150MHz, Fully Differential Amplifier 8-TSOP -40 to 125")
      (libsource (lib "CB3-ECB") (part "THS4551IDGKT"))
    )
    (comp (ref "U6")
      (value "THS4551IDGKT")
      (footprint "TSOP65P490-8AL")
      (description "Low Noise, Precision, 150MHz, Fully Differential Amplifier 8-TSOP -40 to 125")
      (libsource (lib "CB3-ECB") (part "THS4551IDGKT"))
    )
    (comp (ref "U7")
      (value "THS4551IDGKT")
      (footprint "TSOP65P490-8AL")
      (description "Low Noise, Precision, 150MHz, Fully Differential Amplifier 8-TSOP -40 to 125")
      (libsource (lib "CB3-ECB") (part "THS4551IDGKT"))
    )
    (comp (ref "U8")
      (value "THS4551IDGKT")
      (footprint "TSOP65P490-8AL")
      (description "Low Noise, Precision, 150MHz, Fully Differential Amplifier 8-TSOP -40 to 125")
      (libsource (lib "CB3-ECB") (part "THS4551IDGKT"))
    )
    (comp (ref "U9")
      (value "THS4551IDGKT")
      (footprint "TSOP65P490-8AL")
      (description "Low Noise, Precision, 150MHz, Fully Differential Amplifier 8-TSOP -40 to 125")
      (libsource (lib "CB3-ECB") (part "THS4551IDGKT"))
    )
    (comp (ref "U10")
      (value "THS4551IDGKT")
      (footprint "TSOP65P490-8AL")
      (description "Low Noise, Precision, 150MHz, Fully Differential Amplifier 8-TSOP -40 to 125")
      (libsource (lib "CB3-ECB") (part "THS4551IDGKT"))
    )
    (comp (ref "U14")
      (value "NCS325SN2T1G")
      (footprint "SOT23-5AL")
      (description "Single Operational Amplifier, 50 µV Offset, 0.25 µV/°C, Zero-Drift Precision, Low Power")
      (libsource (lib "CB3-ECB") (part "NCS325SN2T1G"))
    )
  )
  (nets
    (net (code "1") (name "+15V") (class "Default")
      (node (ref "C87") (pin "2") (pinfunction "2_2") (pintype "passive"))
      (node (ref "FL2") (pin "3") (pinfunction "OUT/IN_3") (pintype "passive"))
    )
    (net (code "2") (name "+15V_1") (class "Default")
      (node (ref "J100") (pin "1") (pinfunction "1_1") (pintype "passive"))
      (node (ref "J101") (pin "1") (pinfunction "1_1") (pintype "passive"))
      (node (ref "J102") (pin "1") (pinfunction "1_1") (pintype "passive"))
      (node (ref "J103") (pin "1") (pinfunction "1_1") (pintype "passive"))
      (node (ref "J104") (pin "1") (pinfunction "1_1") (pintype "passive"))
      (node (ref "J105") (pin "1") (pinfunction "1_1") (pintype "passive"))
      (node (ref "J106") (pin "1") (pinfunction "1_1") (pintype "passive"))
      (node (ref "J107") (pin "1") (pinfunction "1_1") (pintype "passive"))
      (node (ref "LAN1") (pin "9") (pinfunction "RX-_9") (pintype "passive"))
    )
    (net (code "3") (name "+15V_2") (class "Default")
      (node (ref "J100") (pin "2") (pinfunction "2_2") (pintype "passive"))
      (node (ref "J101") (pin "2") (pinfunction "2_2") (pintype "passive"))
      (node (ref "J102") (pin "2") (pinfunction "2_2") (pintype "passive"))
      (node (ref "J103") (pin "2") (pinfunction "2_2") (pintype "passive"))
      (node (ref "J104") (pin "2") (pinfunction "2_2") (pintype "passive"))
      (node (ref "J105") (pin "2") (pinfunction "2_2") (pintype "passive"))
      (node (ref "J106") (pin "2") (pinfunction "2_2") (pintype "passive"))
      (node (ref "J107") (pin "2") (pinfunction "2_2") (pintype "passive"))
      (node (ref "LAN1") (pin "11") (pinfunction "RX+_11") (pintype "passive"))
    )
    (net (code "4") (name "-15V") (class "Default")
      (node (ref "C88") (pin "1") (pinfunction "1_1") (pintype "passive"))
      (node (ref "FL3") (pin "3") (pinfunction "OUT/IN_3") (pintype "passive"))
    )
    (net (code "5") (name "-15V_1") (class "Default")
      (node (ref "J100") (pin "7") (pinfunction "7_7") (pintype "passive"))
      (node (ref "J101") (pin "7") (pinfunction "7_7") (pintype "passive"))
      (node (ref "J102") (pin "7") (pinfunction "7_7") (pintype "passive"))
      (node (ref "J103") (pin "7") (pinfunction "7_7") (pintype "passive"))
      (node (ref "J104") (pin "7") (pinfunction "7_7") (pintype "passive"))
      (node (ref "J105") (pin "7") (pinfunction "7_7") (pintype "passive"))
      (node (ref "J106") (pin "7") (pinfunction "7_7") (pintype "passive"))
      (node (ref "J107") (pin "7") (pinfunction "7_7") (pintype "passive"))
      (node (ref "LAN1") (pin "14") (pinfunction "TX-_14") (pintype "passive"))
    )
    (net (code "6") (name "-15V_2") (class "Default")
      (node (ref "J100") (pin "8") (pinfunction "8_8") (pintype "passive"))
      (node (ref "J101") (pin "8") (pinfunction "8_8") (pintype "passive"))
      (node (ref "J102") (pin "8") (pinfunction "8_8") (pintype "passive"))
      (node (ref "J103") (pin "8") (pinfunction "8_8") (pintype "passive"))
      (node (ref "J104") (pin "8") (pinfunction "8_8") (pintype "passive"))
      (node (ref "J105") (pin "8") (pinfunction "8_8") (pintype "passive"))
      (node (ref "J106") (pin "8") (pinfunction "8_8") (pintype "passive"))
      (node (ref "J107") (pin "8") (pinfunction "8_8") (pintype "passive"))
      (node (ref "LAN1") (pin "16") (pinfunction "TX+_16") (pintype "passive"))
    )
    (net (code "7") (name "/+15V_FL") (class "Default")
      (node (ref "FL2") (pin "1") (pinfunction "IN/OUT_1") (pintype "passive"))
      (node (ref "LAN1") (pin "10") (pinfunction "RXCT_10") (pintype "passive"))
    )
    (net (code "8") (name "/-15V_FL") (class "Default")
      (node (ref "FL3") (pin "1") (pinfunction "IN/OUT_1") (pintype "passive"))
      (node (ref "LAN1") (pin "15") (pinfunction "TXCT_15") (pintype "passive"))
    )
    (net (code "9") (name "/2V5REFBUF") (class "Default")
      (node (ref "C20") (pin "2") (pinfunction "2_2") (pintype "passive"))
      (node (ref "C25") (pin "2") (pinfunction "2_2") (pintype "passive"))
      (node (ref "C30") (pin "2") (pinfunction "2_2") (pintype "passive"))
      (node (ref "C33") (pin "2") (pinfunction "2_2") (pintype "passive"))
      (node (ref "C40") (pin "2") (pinfunction "2_2") (pintype "passive"))
      (node (ref "C43") (pin "2") (pinfunction "2_2") (pintype "passive"))
      (node (ref "C50") (pin "2") (pinfunction "2_2") (pintype "passive"))
      (node (ref "C53") (pin "2") (pinfunction "2_2") (pintype "passive"))
      (node (ref "C81") (pin "2") (pinfunction "2_2") (pintype "passive"))
      (node (ref "R80") (pin "2") (pinfunction "2_2") (pintype "passive"))
      (node (ref "U10") (pin "2") (pinfunction "Vocm_2") (pintype "passive"))
      (node (ref "U3") (pin "2") (pinfunction "Vocm_2") (pintype "passive"))
      (node (ref "U4") (pin "2") (pinfunction "Vocm_2") (pintype "passive"))
      (node (ref "U5") (pin "2") (pinfunction "Vocm_2") (pintype "passive"))
      (node (ref "U6") (pin "2") (pinfunction "Vocm_2") (pintype "passive"))
      (node (ref "U7") (pin "2") (pinfunction "Vocm_2") (pintype "passive"))
      (node (ref "U8") (pin "2") (pinfunction "Vocm_2") (pintype "passive"))
      (node (ref "U9") (pin "2") (pinfunction "Vocm_2") (pintype "passive"))
    )
    (net (code "10") (name "/2V5REFOUT") (class "Default")
      (node (ref "R81") (pin "1") (pinfunction "1_1") (pintype "passive"))
    )
    (net (code "11") (name "/ADC0_N") (class "Default")
      (node (ref "J100") (pin "5") (pinfunction "5_5") (pintype "passive"))
      (node (ref "R24") (pin "3") (pinfunction "3_3") (pintype "passive"))
      (node (ref "R76") (pin "2") (pinfunction "2_2") (pintype "passive"))
    )
    (net (code "12") (name "/ADC0_P") (class "Default")
      (node (ref "J100") (pin "4") (pinfunction "4_4") (pintype "passive"))
      (node (ref "R24") (pin "2") (pinfunction "2_2") (pintype "passive"))
      (node (ref "R77") (pin "2") (pinfunction "2_2") (pintype "passive"))
    )
    (net (code "13") (name "/ADC1_N") (class "Default")
      (node (ref "J101") (pin "5") (pinfunction "5_5") (pintype "passive"))
      (node (ref "R26") (pin "3") (pinfunction "3_3") (pintype "passive"))
      (node (ref "R72") (pin "2") (pinfunction "2_2") (pintype "passive"))
    )
    (net (code "14") (name "/ADC1_P") (class "Default")
      (node (ref "J101") (pin "4") (pinfunction "4_4") (pintype "passive"))
      (node (ref "R26") (pin "2") (pinfunction "2_2") (pintype "passive"))
      (node (ref "R73") (pin "2") (pinfunction "2_2") (pintype "passive"))
    )
    (net (code "15") (name "/ADC2_N") (class "Default")
      (node (ref "J102") (pin "5") (pinfunction "5_5") (pintype "passive"))
      (node (ref "R28") (pin "3") (pinfunction "3_3") (pintype "passive"))
      (node (ref "R38") (pin "2") (pinfunction "2_2") (pintype "passive"))
    )
    (net (code "16") (name "/ADC2_P") (class "Default")
      (node (ref "J102") (pin "4") (pinfunction "4_4") (pintype "passive"))
      (node (ref "R28") (pin "2") (pinfunction "2_2") (pintype "passive"))
      (node (ref "R39") (pin "2") (pinfunction "2_2") (pintype "passive"))
    )
    (net (code "17") (name "/ADC3_N") (class "Default")
      (node (ref "J103") (pin "5") (pinfunction "5_5") (pintype "passive"))
      (node (ref "R3") (pin "2") (pinfunction "2_2") (pintype "passive"))
      (node (ref "R30") (pin "3") (pinfunction "3_3") (pintype "passive"))
    )
    (net (code "18") (name "/ADC3_P") (class "Default")
      (node (ref "J103") (pin "4") (pinfunction "4_4") (pintype "passive"))
      (node (ref "R30") (pin "2") (pinfunction "2_2") (pintype "passive"))
      (node (ref "R4") (pin "2") (pinfunction "2_2") (pintype "passive"))
    )
    (net (code "19") (name "/ADC4_N") (class "Default")
      (node (ref "J104") (pin "5") (pinfunction "5_5") (pintype "passive"))
      (node (ref "R25") (pin "3") (pinfunction "3_3") (pintype "passive"))
      (node (ref "R78") (pin "2") (pinfunction "2_2") (pintype "passive"))
    )
    (net (code "20") (name "/ADC4_P") (class "Default")
      (node (ref "J104") (pin "4") (pinfunction "4_4") (pintype "passive"))
      (node (ref "R25") (pin "2") (pinfunction "2_2") (pintype "passive"))
      (node (ref "R79") (pin "2") (pinfunction "2_2") (pintype "passive"))
    )
    (net (code "21") (name "/ADC5_N") (class "Default")
      (node (ref "J105") (pin "5") (pinfunction "5_5") (pintype "passive"))
      (node (ref "R27") (pin "3") (pinfunction "3_3") (pintype "passive"))
      (node (ref "R74") (pin "2") (pinfunction "2_2") (pintype "passive"))
    )
    (net (code "22") (name "/ADC5_P") (class "Default")
      (node (ref "J105") (pin "4") (pinfunction "4_4") (pintype "passive"))
      (node (ref "R27") (pin "2") (pinfunction "2_2") (pintype "passive"))
      (node (ref "R75") (pin "2") (pinfunction "2_2") (pintype "passive"))
    )
    (net (code "23") (name "/ADC6_N") (class "Default")
      (node (ref "J106") (pin "5") (pinfunction "5_5") (pintype "passive"))
      (node (ref "R29") (pin "3") (pinfunction "3_3") (pintype "passive"))
      (node (ref "R40") (pin "2") (pinfunction "2_2") (pintype "passive"))
    )
    (net (code "24") (name "/ADC6_P") (class "Default")
      (node (ref "J106") (pin "4") (pinfunction "4_4") (pintype "passive"))
      (node (ref "R29") (pin "2") (pinfunction "2_2") (pintype "passive"))
      (node (ref "R71") (pin "2") (pinfunction "2_2") (pintype "passive"))
    )
    (net (code "25") (name "/ADC7_N") (class "Default")
      (node (ref "J107") (pin "5") (pinfunction "5_5") (pintype "passive"))
      (node (ref "R31") (pin "3") (pinfunction "3_3") (pintype "passive"))
      (node (ref "R35") (pin "2") (pinfunction "2_2") (pintype "passive"))
    )
    (net (code "26") (name "/ADC7_P") (class "Default")
      (node (ref "J107") (pin "4") (pinfunction "4_4") (pintype "passive"))
      (node (ref "R31") (pin "2") (pinfunction "2_2") (pintype "passive"))
      (node (ref "R37") (pin "2") (pinfunction "2_2") (pintype "passive"))
    )
    (net (code "27") (name "/AIN0_N") (class "Default")
      (node (ref "C16") (pin "2") (pinfunction "2_2") (pintype "passive"))
      (node (ref "JX3") (pin "29") (pinfunction "AIN_0N_29") (pintype "input"))
      (node (ref "R24") (pin "1") (pinfunction "1_1") (pintype "passive"))
      (node (ref "TP106") (pin "1") (pinfunction "TP_1") (pintype "passive"))
      (node (ref "U3") (pin "5") (pinfunction "-_5") (pintype "passive"))
    )
    (net (code "28") (name "/AIN0_P") (class "Default")
      (node (ref "C23") (pin "2") (pinfunction "2_2") (pintype "passive"))
      (node (ref "JX3") (pin "28") (pinfunction "AIN_0P_28") (pintype "input"))
      (node (ref "R24") (pin "4") (pinfunction "4_4") (pintype "passive"))
      (node (ref "TP108") (pin "1") (pinfunction "TP_1") (pintype "passive"))
      (node (ref "U3") (pin "4") (pinfunction "+_4") (pintype "passive"))
    )
    (net (code "29") (name "/AIN1_N") (class "Default")
      (node (ref "C26") (pin "2") (pinfunction "2_2") (pintype "passive"))
      (node (ref "JX3") (pin "26") (pinfunction "AIN_1N_26") (pintype "input"))
      (node (ref "R26") (pin "1") (pinfunction "1_1") (pintype "passive"))
      (node (ref "TP110") (pin "1") (pinfunction "TP_1") (pintype "passive"))
      (node (ref "U5") (pin "5") (pinfunction "-_5") (pintype "passive"))
    )
    (net (code "30") (name "/AIN1_P") (class "Default")
      (node (ref "C34") (pin "2") (pinfunction "2_2") (pintype "passive"))
      (node (ref "JX3") (pin "25") (pinfunction "AIN_1P_25") (pintype "input"))
      (node (ref "R26") (pin "4") (pinfunction "4_4") (pintype "passive"))
      (node (ref "TP112") (pin "1") (pinfunction "TP_1") (pintype "passive"))
      (node (ref "U5") (pin "4") (pinfunction "+_4") (pintype "passive"))
    )
    (net (code "31") (name "/AIN2_N") (class "Default")
      (node (ref "C36") (pin "2") (pinfunction "2_2") (pintype "passive"))
      (node (ref "JX3") (pin "23") (pinfunction "AIN_2N_23") (pintype "input"))
      (node (ref "R28") (pin "1") (pinfunction "1_1") (pintype "passive"))
      (node (ref "TP114") (pin "1") (pinfunction "TP_1") (pintype "passive"))
      (node (ref "U7") (pin "5") (pinfunction "-_5") (pintype "passive"))
    )
    (net (code "32") (name "/AIN2_P") (class "Default")
      (node (ref "C44") (pin "2") (pinfunction "2_2") (pintype "passive"))
      (node (ref "JX3") (pin "22") (pinfunction "AIN_2P_22") (pintype "input"))
      (node (ref "R28") (pin "4") (pinfunction "4_4") (pintype "passive"))
      (node (ref "TP116") (pin "1") (pinfunction "TP_1") (pintype "passive"))
      (node (ref "U7") (pin "4") (pinfunction "+_4") (pintype "passive"))
    )
    (net (code "33") (name "/AIN3_N") (class "Default")
      (node (ref "C48") (pin "2") (pinfunction "2_2") (pintype "passive"))
      (node (ref "JX3") (pin "20") (pinfunction "AIN_3N_20") (pintype "input"))
      (node (ref "R30") (pin "1") (pinfunction "1_1") (pintype "passive"))
      (node (ref "TP118") (pin "1") (pinfunction "TP_1") (pintype "passive"))
      (node (ref "U9") (pin "5") (pinfunction "-_5") (pintype "passive"))
    )
    (net (code "34") (name "/AIN3_P") (class "Default")
      (node (ref "C54") (pin "2") (pinfunction "2_2") (pintype "passive"))
      (node (ref "JX3") (pin "19") (pinfunction "AIN_3P_19") (pintype "input"))
      (node (ref "R30") (pin "4") (pinfunction "4_4") (pintype "passive"))
      (node (ref "TP120") (pin "1") (pinfunction "TP_1") (pintype "passive"))
      (node (ref "U9") (pin "4") (pinfunction "+_4") (pintype "passive"))
    )
    (net (code "35") (name "/AIN4_N") (class "Default")
      (node (ref "C17") (pin "2") (pinfunction "2_2") (pintype "passive"))
      (node (ref "JX3") (pin "32") (pinfunction "AIN_4N_32") (pintype "input"))
      (node (ref "R25") (pin "1") (pinfunction "1_1") (pintype "passive"))
      (node (ref "TP107") (pin "1") (pinfunction "TP_1") (pintype "passive"))
      (node (ref "U4") (pin "5") (pinfunction "-_5") (pintype "passive"))
    )
    (net (code "36") (name "/AIN4_P") (class "Default")
      (node (ref "C24") (pin "2") (pinfunction "2_2") (pintype "passive"))
      (node (ref "JX3") (pin "33") (pinfunction "AIN_4P_33") (pintype "input"))
      (node (ref "R25") (pin "4") (pinfunction "4_4") (pintype "passive"))
      (node (ref "TP109") (pin "1") (pinfunction "TP_1") (pintype "passive"))
      (node (ref "U4") (pin "4") (pinfunction "+_4") (pintype "passive"))
    )
    (net (code "37") (name "/AIN5_N") (class "Default")
      (node (ref "C27") (pin "2") (pinfunction "2_2") (pintype "passive"))
      (node (ref "JX3") (pin "35") (pinfunction "AIN_5N_35") (pintype "input"))
      (node (ref "R27") (pin "1") (pinfunction "1_1") (pintype "passive"))
      (node (ref "TP111") (pin "1") (pinfunction "TP_1") (pintype "passive"))
      (node (ref "U6") (pin "5") (pinfunction "-_5") (pintype "passive"))
    )
    (net (code "38") (name "/AIN5_P") (class "Default")
      (node (ref "C35") (pin "2") (pinfunction "2_2") (pintype "passive"))
      (node (ref "JX3") (pin "36") (pinfunction "AIN_5P_36") (pintype "input"))
      (node (ref "R27") (pin "4") (pinfunction "4_4") (pintype "passive"))
      (node (ref "TP113") (pin "1") (pinfunction "TP_1") (pintype "passive"))
      (node (ref "U6") (pin "4") (pinfunction "+_4") (pintype "passive"))
    )
    (net (code "39") (name "/AIN6_N") (class "Default")
      (node (ref "C37") (pin "2") (pinfunction "2_2") (pintype "passive"))
      (node (ref "JX3") (pin "38") (pinfunction "AIN_6N_38") (pintype "input"))
      (node (ref "R29") (pin "1") (pinfunction "1_1") (pintype "passive"))
      (node (ref "TP115") (pin "1") (pinfunction "TP_1") (pintype "passive"))
      (node (ref "U8") (pin "5") (pinfunction "-_5") (pintype "passive"))
    )
    (net (code "40") (name "/AIN6_P") (class "Default")
      (node (ref "C45") (pin "2") (pinfunction "2_2") (pintype "passive"))
      (node (ref "JX3") (pin "39") (pinfunction "AIN_6P_39") (pintype "input"))
      (node (ref "R29") (pin "4") (pinfunction "4_4") (pintype "passive"))
      (node (ref "TP117") (pin "1") (pinfunction "TP_1") (pintype "passive"))
      (node (ref "U8") (pin "4") (pinfunction "+_4") (pintype "passive"))
    )
    (net (code "41") (name "/AIN7_N") (class "Default")
      (node (ref "C49") (pin "2") (pinfunction "2_2") (pintype "passive"))
      (node (ref "JX3") (pin "41") (pinfunction "AIN_7N_41") (pintype "input"))
      (node (ref "R31") (pin "1") (pinfunction "1_1") (pintype "passive"))
      (node (ref "TP119") (pin "1") (pinfunction "TP_1") (pintype "passive"))
      (node (ref "U10") (pin "5") (pinfunction "-_5") (pintype "passive"))
    )
    (net (code "42") (name "/AIN7_P") (class "Default")
      (node (ref "C55") (pin "2") (pinfunction "2_2") (pintype "passive"))
      (node (ref "JX3") (pin "42") (pinfunction "AIN_7P_42") (pintype "input"))
      (node (ref "R31") (pin "4") (pinfunction "4_4") (pintype "passive"))
      (node (ref "TP121") (pin "1") (pinfunction "TP_1") (pintype "passive"))
      (node (ref "U10") (pin "4") (pinfunction "+_4") (pintype "passive"))
    )
    (net (code "43") (name "5V2") (class "Default")
      (node (ref "C18") (pin "2") (pinfunction "2_2") (pintype "passive"))
      (node (ref "C19") (pin "2") (pinfunction "2_2") (pintype "passive"))
      (node (ref "C21") (pin "2") (pinfunction "2_2") (pintype "passive"))
      (node (ref "C22") (pin "2") (pinfunction "2_2") (pintype "passive"))
      (node (ref "C28") (pin "2") (pinfunction "2_2") (pintype "passive"))
      (node (ref "C29") (pin "2") (pinfunction "2_2") (pintype "passive"))
      (node (ref "C31") (pin "2") (pinfunction "2_2") (pintype "passive"))
      (node (ref "C32") (pin "2") (pinfunction "2_2") (pintype "passive"))
      (node (ref "C38") (pin "2") (pinfunction "2_2") (pintype "passive"))
      (node (ref "C39") (pin "2") (pinfunction "2_2") (pintype "passive"))
      (node (ref "C41") (pin "2") (pinfunction "2_2") (pintype "passive"))
      (node (ref "C42") (pin "2") (pinfunction "2_2") (pintype "passive"))
      (node (ref "C46") (pin "2") (pinfunction "2_2") (pintype "passive"))
      (node (ref "C47") (pin "2") (pinfunction "2_2") (pintype "passive"))
      (node (ref "C51") (pin "2") (pinfunction "2_2") (pintype "passive"))
      (node (ref "C52") (pin "2") (pinfunction "2_2") (pintype "passive"))
      (node (ref "C77") (pin "2") (pinfunction "2_2") (pintype "passive"))
      (node (ref "C79") (pin "2") (pinfunction "2_2") (pintype "passive"))
      (node (ref "JX3") (pin "10") (pinfunction "5.2V_10") (pintype "power_in"))
      (node (ref "JX3") (pin "11") (pinfunction "5.2V_11") (pintype "power_in"))
      (node (ref "JX3") (pin "13") (pinfunction "5.2V_13") (pintype "power_in"))
      (node (ref "JX3") (pin "14") (pinfunction "5.2V_14") (pintype "power_in"))
      (node (ref "JX3") (pin "16") (pinfunction "5.2V_16") (pintype "power_in"))
      (node (ref "JX3") (pin "17") (pinfunction "5.2V_17") (pintype "power_in"))
      (node (ref "JX3") (pin "44") (pinfunction "5.2V_44") (pintype "power_in"))
      (node (ref "JX3") (pin "45") (pinfunction "5.2V_45") (pintype "power_in"))
      (node (ref "JX3") (pin "47") (pinfunction "5.2V_47") (pintype "power_in"))
      (node (ref "JX3") (pin "48") (pinfunction "5.2V_48") (pintype "power_in"))
      (node (ref "JX3") (pin "50") (pinfunction "5.2V_50") (pintype "power_in"))
      (node (ref "JX3") (pin "51") (pinfunction "5.2V_51") (pintype "power_in"))
      (node (ref "U10") (pin "3") (pinfunction "Vs+_3") (pintype "passive"))
      (node (ref "U10") (pin "7") (pinfunction "~{PD}_7") (pintype "passive"))
      (node (ref "U14") (pin "5") (pinfunction "VDD_5") (pintype "power_in"))
      (node (ref "U3") (pin "3") (pinfunction "Vs+_3") (pintype "passive"))
      (node (ref "U3") (pin "7") (pinfunction "~{PD}_7") (pintype "passive"))
      (node (ref "U4") (pin "3") (pinfunction "Vs+_3") (pintype "passive"))
      (node (ref "U4") (pin "7") (pinfunction "~{PD}_7") (pintype "passive"))
      (node (ref "U5") (pin "3") (pinfunction "Vs+_3") (pintype "passive"))
      (node (ref "U5") (pin "7") (pinfunction "~{PD}_7") (pintype "passive"))
      (node (ref "U6") (pin "3") (pinfunction "Vs+_3") (pintype "passive"))
      (node (ref "U6") (pin "7") (pinfunction "~{PD}_7") (pintype "passive"))
      (node (ref "U7") (pin "3") (pinfunction "Vs+_3") (pintype "passive"))
      (node (ref "U7") (pin "7") (pinfunction "~{PD}_7") (pintype "passive"))
      (node (ref "U8") (pin "3") (pinfunction "Vs+_3") (pintype "passive"))
      (node (ref "U8") (pin "7") (pinfunction "~{PD}_7") (pintype "passive"))
      (node (ref "U9") (pin "3") (pinfunction "Vs+_3") (pintype "passive"))
      (node (ref "U9") (pin "7") (pinfunction "~{PD}_7") (pintype "passive"))
    )
    (net (code "44") (name "GND") (class "Default")
      (node (ref "C18") (pin "1") (pinfunction "1_1") (pintype "passive"))
      (node (ref "C19") (pin "1") (pinfunction "1_1") (pintype "passive"))
      (node (ref "C20") (pin "1") (pinfunction "1_1") (pintype "passive"))
      (node (ref "C21") (pin "1") (pinfunction "1_1") (pintype "passive"))
      (node (ref "C22") (pin "1") (pinfunction "1_1") (pintype "passive"))
      (node (ref "C25") (pin "1") (pinfunction "1_1") (pintype "passive"))
      (node (ref "C28") (pin "1") (pinfunction "1_1") (pintype "passive"))
      (node (ref "C29") (pin "1") (pinfunction "1_1") (pintype "passive"))
      (node (ref "C30") (pin "1") (pinfunction "1_1") (pintype "passive"))
      (node (ref "C31") (pin "1") (pinfunction "1_1") (pintype "passive"))
      (node (ref "C32") (pin "1") (pinfunction "1_1") (pintype "passive"))
      (node (ref "C33") (pin "1") (pinfunction "1_1") (pintype "passive"))
      (node (ref "C38") (pin "1") (pinfunction "1_1") (pintype "passive"))
      (node (ref "C39") (pin "1") (pinfunction "1_1") (pintype "passive"))
      (node (ref "C40") (pin "1") (pinfunction "1_1") (pintype "passive"))
      (node (ref "C41") (pin "1") (pinfunction "1_1") (pintype "passive"))
      (node (ref "C42") (pin "1") (pinfunction "1_1") (pintype "passive"))
      (node (ref "C43") (pin "1") (pinfunction "1_1") (pintype "passive"))
      (node (ref "C46") (pin "1") (pinfunction "1_1") (pintype "passive"))
      (node (ref "C47") (pin "1") (pinfunction "1_1") (pintype "passive"))
      (node (ref "C50") (pin "1") (pinfunction "1_1") (pintype "passive"))
      (node (ref "C51") (pin "1") (pinfunction "1_1") (pintype "passive"))
      (node (ref "C52") (pin "1") (pinfunction "1_1") (pintype "passive"))
      (node (ref "C53") (pin "1") (pinfunction "1_1") (pintype "passive"))
      (node (ref "C77") (pin "1") (pinfunction "1_1") (pintype "passive"))
      (node (ref "C79") (pin "1") (pinfunction "1_1") (pintype "passive"))
      (node (ref "C80") (pin "1") (pinfunction "1_1") (pintype "passive"))
      (node (ref "C81") (pin "1") (pinfunction "1_1") (pintype "passive"))
      (node (ref "C87") (pin "1") (pinfunction "1_1") (pintype "passive"))
      (node (ref "C88") (pin "2") (pinfunction "2_2") (pintype "passive"))
      (node (ref "FL2") (pin "2") (pinfunction "GND_1_2") (pintype "passive"))
      (node (ref "FL2") (pin "4") (pinfunction "GND_2_4") (pintype "passive"))
      (node (ref "FL3") (pin "2") (pinfunction "GND_1_2") (pintype "passive"))
      (node (ref "FL3") (pin "4") (pinfunction "GND_2_4") (pintype "passive"))
      (node (ref "J100") (pin "10") (pinfunction "MNT_2_10") (pintype "passive"))
      (node (ref "J100") (pin "3") (pinfunction "3_3") (pintype "passive"))
      (node (ref "J100") (pin "6") (pinfunction "6_6") (pintype "passive"))
      (node (ref "J100") (pin "9") (pinfunction "MNT_1_9") (pintype "passive"))
      (node (ref "J101") (pin "10") (pinfunction "MNT_2_10") (pintype "passive"))
      (node (ref "J101") (pin "3") (pinfunction "3_3") (pintype "passive"))
      (node (ref "J101") (pin "6") (pinfunction "6_6") (pintype "passive"))
      (node (ref "J101") (pin "9") (pinfunction "MNT_1_9") (pintype "passive"))
      (node (ref "J102") (pin "10") (pinfunction "MNT_2_10") (pintype "passive"))
      (node (ref "J102") (pin "3") (pinfunction "3_3") (pintype "passive"))
      (node (ref "J102") (pin "6") (pinfunction "6_6") (pintype "passive"))
      (node (ref "J102") (pin "9") (pinfunction "MNT_1_9") (pintype "passive"))
      (node (ref "J103") (pin "10") (pinfunction "MNT_2_10") (pintype "passive"))
      (node (ref "J103") (pin "3") (pinfunction "3_3") (pintype "passive"))
      (node (ref "J103") (pin "6") (pinfunction "6_6") (pintype "passive"))
      (node (ref "J103") (pin "9") (pinfunction "MNT_1_9") (pintype "passive"))
      (node (ref "J104") (pin "10") (pinfunction "MNT_2_10") (pintype "passive"))
      (node (ref "J104") (pin "3") (pinfunction "3_3") (pintype "passive"))
      (node (ref "J104") (pin "6") (pinfunction "6_6") (pintype "passive"))
      (node (ref "J104") (pin "9") (pinfunction "MNT_1_9") (pintype "passive"))
      (node (ref "J105") (pin "10") (pinfunction "MNT_2_10") (pintype "passive"))
      (node (ref "J105") (pin "3") (pinfunction "3_3") (pintype "passive"))
      (node (ref "J105") (pin "6") (pinfunction "6_6") (pintype "passive"))
      (node (ref "J105") (pin "9") (pinfunction "MNT_1_9") (pintype "passive"))
      (node (ref "J106") (pin "10") (pinfunction "MNT_2_10") (pintype "passive"))
      (node (ref "J106") (pin "3") (pinfunction "3_3") (pintype "passive"))
      (node (ref "J106") (pin "6") (pinfunction "6_6") (pintype "passive"))
      (node (ref "J106") (pin "9") (pinfunction "MNT_1_9") (pintype "passive"))
      (node (ref "J107") (pin "10") (pinfunction "MNT_2_10") (pintype "passive"))
      (node (ref "J107") (pin "3") (pinfunction "3_3") (pintype "passive"))
      (node (ref "J107") (pin "6") (pinfunction "6_6") (pintype "passive"))
      (node (ref "J107") (pin "9") (pinfunction "MNT_1_9") (pintype "passive"))
      (node (ref "JX3") (pin "1") (pinfunction "GND_1") (pintype "power_in"))
      (node (ref "JX3") (pin "12") (pinfunction "GND_12") (pintype "power_in"))
      (node (ref "JX3") (pin "15") (pinfunction "GND_15") (pintype "power_in"))
      (node (ref "JX3") (pin "18") (pinfunction "GND_18") (pintype "power_in"))
      (node (ref "JX3") (pin "21") (pinfunction "GND_21") (pintype "power_in"))
      (node (ref "JX3") (pin "24") (pinfunction "GND_24") (pintype "power_in"))
      (node (ref "JX3") (pin "27") (pinfunction "GND_27") (pintype "power_in"))
      (node (ref "JX3") (pin "30") (pinfunction "GND_30") (pintype "power_in"))
      (node (ref "JX3") (pin "31") (pinfunction "GND_31") (pintype "power_in"))
      (node (ref "JX3") (pin "34") (pinfunction "GND_34") (pintype "power_in"))
      (node (ref "JX3") (pin "37") (pinfunction "GND_37") (pintype "power_in"))
      (node (ref "JX3") (pin "4") (pinfunction "GND_4") (pintype "power_in"))
      (node (ref "JX3") (pin "40") (pinfunction "GND_40") (pintype "power_in"))
      (node (ref "JX3") (pin "43") (pinfunction "GND_43") (pintype "power_in"))
      (node (ref "JX3") (pin "46") (pinfunction "GND_46") (pintype "power_in"))
      (node (ref "JX3") (pin "49") (pinfunction "GND_49") (pintype "power_in"))
      (node (ref "JX3") (pin "52") (pinfunction "GND_52") (pintype "power_in"))
      (node (ref "JX3") (pin "57") (pinfunction "GND_57") (pintype "power_in"))
      (node (ref "JX3") (pin "60") (pinfunction "GND_60") (pintype "power_in"))
      (node (ref "JX3") (pin "9") (pinfunction "GND_9") (pintype "power_in"))
      (node (ref "R3") (pin "1") (pinfunction "1_1") (pintype "passive"))
      (node (ref "R35") (pin "1") (pinfunction "1_1") (pintype "passive"))
      (node (ref "R37") (pin "1") (pinfunction "1_1") (pintype "passive"))
      (node (ref "R38") (pin "1") (pinfunction "1_1") (pintype "passive"))
      (node (ref "R39") (pin "1") (pinfunction "1_1") (pintype "passive"))
      (node (ref "R4") (pin "1") (pinfunction "1_1") (pintype "passive"))
      (node (ref "R40") (pin "1") (pinfunction "1_1") (pintype "passive"))
      (node (ref "R71") (pin "1") (pinfunction "1_1") (pintype "passive"))
      (node (ref "R72") (pin "1") (pinfunction "1_1") (pintype "passive"))
      (node (ref "R73") (pin "1") (pinfunction "1_1") (pintype "passive"))
      (node (ref "R74") (pin "1") (pinfunction "1_1") (pintype "passive"))
      (node (ref "R75") (pin "1") (pinfunction "1_1") (pintype "passive"))
      (node (ref "R76") (pin "1") (pinfunction "1_1") (pintype "passive"))
      (node (ref "R77") (pin "1") (pinfunction "1_1") (pintype "passive"))
      (node (ref "R78") (pin "1") (pinfunction "1_1") (pintype "passive"))
      (node (ref "R79") (pin "1") (pinfunction "1_1") (pintype "passive"))
      (node (ref "U10") (pin "6") (pinfunction "Vs-_6") (pintype "passive"))
      (node (ref "U14") (pin "2") (pinfunction "VSS_2") (pintype "power_in"))
      (node (ref "U3") (pin "6") (pinfunction "Vs-_6") (pintype "passive"))
      (node (ref "U4") (pin "6") (pinfunction "Vs-_6") (pintype "passive"))
      (node (ref "U5") (pin "6") (pinfunction "Vs-_6") (pintype "passive"))
      (node (ref "U6") (pin "6") (pinfunction "Vs-_6") (pintype "passive"))
      (node (ref "U7") (pin "6") (pinfunction "Vs-_6") (pintype "passive"))
      (node (ref "U8") (pin "6") (pinfunction "Vs-_6") (pintype "passive"))
      (node (ref "U9") (pin "6") (pinfunction "Vs-_6") (pintype "passive"))
    )
    (net (code "45") (name "Net-(C16-Pad1)") (class "Default")
      (node (ref "C16") (pin "1") (pinfunction "1_1") (pintype "passive"))
      (node (ref "R24") (pin "7") (pinfunction "7_7") (pintype "passive"))
      (node (ref "R24") (pin "8") (pinfunction "8_8") (pintype "passive"))
      (node (ref "U3") (pin "8") (pinfunction "+_8") (pintype "passive"))
    )
    (net (code "46") (name "Net-(C17-Pad1)") (class "Default")
      (node (ref "C17") (pin "1") (pinfunction "1_1") (pintype "passive"))
      (node (ref "R25") (pin "7") (pinfunction "7_7") (pintype "passive"))
      (node (ref "R25") (pin "8") (pinfunction "8_8") (pintype "passive"))
      (node (ref "U4") (pin "8") (pinfunction "+_8") (pintype "passive"))
    )
    (net (code "47") (name "Net-(C23-Pad1)") (class "Default")
      (node (ref "C23") (pin "1") (pinfunction "1_1") (pintype "passive"))
      (node (ref "R24") (pin "5") (pinfunction "5_5") (pintype "passive"))
      (node (ref "R24") (pin "6") (pinfunction "6_6") (pintype "passive"))
      (node (ref "U3") (pin "1") (pinfunction "-_1") (pintype "passive"))
    )
    (net (code "48") (name "Net-(C24-Pad1)") (class "Default")
      (node (ref "C24") (pin "1") (pinfunction "1_1") (pintype "passive"))
      (node (ref "R25") (pin "5") (pinfunction "5_5") (pintype "passive"))
      (node (ref "R25") (pin "6") (pinfunction "6_6") (pintype "passive"))
      (node (ref "U4") (pin "1") (pinfunction "-_1") (pintype "passive"))
    )
    (net (code "49") (name "Net-(C26-Pad1)") (class "Default")
      (node (ref "C26") (pin "1") (pinfunction "1_1") (pintype "passive"))
      (node (ref "R26") (pin "7") (pinfunction "7_7") (pintype "passive"))
      (node (ref "R26") (pin "8") (pinfunction "8_8") (pintype "passive"))
      (node (ref "U5") (pin "8") (pinfunction "+_8") (pintype "passive"))
    )
    (net (code "50") (name "Net-(C27-Pad1)") (class "Default")
      (node (ref "C27") (pin "1") (pinfunction "1_1") (pintype "passive"))
      (node (ref "R27") (pin "7") (pinfunction "7_7") (pintype "passive"))
      (node (ref "R27") (pin "8") (pinfunction "8_8") (pintype "passive"))
      (node (ref "U6") (pin "8") (pinfunction "+_8") (pintype "passive"))
    )
    (net (code "51") (name "Net-(C34-Pad1)") (class "Default")
      (node (ref "C34") (pin "1") (pinfunction "1_1") (pintype "passive"))
      (node (ref "R26") (pin "5") (pinfunction "5_5") (pintype "passive"))
      (node (ref "R26") (pin "6") (pinfunction "6_6") (pintype "passive"))
      (node (ref "U5") (pin "1") (pinfunction "-_1") (pintype "passive"))
    )
    (net (code "52") (name "Net-(C35-Pad1)") (class "Default")
      (node (ref "C35") (pin "1") (pinfunction "1_1") (pintype "passive"))
      (node (ref "R27") (pin "5") (pinfunction "5_5") (pintype "passive"))
      (node (ref "R27") (pin "6") (pinfunction "6_6") (pintype "passive"))
      (node (ref "U6") (pin "1") (pinfunction "-_1") (pintype "passive"))
    )
    (net (code "53") (name "Net-(C36-Pad1)") (class "Default")
      (node (ref "C36") (pin "1") (pinfunction "1_1") (pintype "passive"))
      (node (ref "R28") (pin "7") (pinfunction "7_7") (pintype "passive"))
      (node (ref "R28") (pin "8") (pinfunction "8_8") (pintype "passive"))
      (node (ref "U7") (pin "8") (pinfunction "+_8") (pintype "passive"))
    )
    (net (code "54") (name "Net-(C37-Pad1)") (class "Default")
      (node (ref "C37") (pin "1") (pinfunction "1_1") (pintype "passive"))
      (node (ref "R29") (pin "7") (pinfunction "7_7") (pintype "passive"))
      (node (ref "R29") (pin "8") (pinfunction "8_8") (pintype "passive"))
      (node (ref "U8") (pin "8") (pinfunction "+_8") (pintype "passive"))
    )
    (net (code "55") (name "Net-(C44-Pad1)") (class "Default")
      (node (ref "C44") (pin "1") (pinfunction "1_1") (pintype "passive"))
      (node (ref "R28") (pin "5") (pinfunction "5_5") (pintype "passive"))
      (node (ref "R28") (pin "6") (pinfunction "6_6") (pintype "passive"))
      (node (ref "U7") (pin "1") (pinfunction "-_1") (pintype "passive"))
    )
    (net (code "56") (name "Net-(C45-Pad1)") (class "Default")
      (node (ref "C45") (pin "1") (pinfunction "1_1") (pintype "passive"))
      (node (ref "R29") (pin "5") (pinfunction "5_5") (pintype "passive"))
      (node (ref "R29") (pin "6") (pinfunction "6_6") (pintype "passive"))
      (node (ref "U8") (pin "1") (pinfunction "-_1") (pintype "passive"))
    )
    (net (code "57") (name "Net-(C48-Pad1)") (class "Default")
      (node (ref "C48") (pin "1") (pinfunction "1_1") (pintype "passive"))
      (node (ref "R30") (pin "7") (pinfunction "7_7") (pintype "passive"))
      (node (ref "R30") (pin "8") (pinfunction "8_8") (pintype "passive"))
      (node (ref "U9") (pin "8") (pinfunction "+_8") (pintype "passive"))
    )
    (net (code "58") (name "Net-(C49-Pad1)") (class "Default")
      (node (ref "C49") (pin "1") (pinfunction "1_1") (pintype "passive"))
      (node (ref "R31") (pin "7") (pinfunction "7_7") (pintype "passive"))
      (node (ref "R31") (pin "8") (pinfunction "8_8") (pintype "passive"))
      (node (ref "U10") (pin "8") (pinfunction "+_8") (pintype "passive"))
    )
    (net (code "59") (name "Net-(C54-Pad1)") (class "Default")
      (node (ref "C54") (pin "1") (pinfunction "1_1") (pintype "passive"))
      (node (ref "R30") (pin "5") (pinfunction "5_5") (pintype "passive"))
      (node (ref "R30") (pin "6") (pinfunction "6_6") (pintype "passive"))
      (node (ref "U9") (pin "1") (pinfunction "-_1") (pintype "passive"))
    )
    (net (code "60") (name "Net-(C55-Pad1)") (class "Default")
      (node (ref "C55") (pin "1") (pinfunction "1_1") (pintype "passive"))
      (node (ref "R31") (pin "5") (pinfunction "5_5") (pintype "passive"))
      (node (ref "R31") (pin "6") (pinfunction "6_6") (pintype "passive"))
      (node (ref "U10") (pin "1") (pinfunction "-_1") (pintype "passive"))
    )
    (net (code "61") (name "Net-(U14A-IN+)") (class "Default")
      (node (ref "C80") (pin "2") (pinfunction "2_2") (pintype "passive"))
      (node (ref "R81") (pin "2") (pinfunction "2_2") (pintype "passive"))
      (node (ref "U14") (pin "3") (pinfunction "IN+_3") (pintype "passive"))
    )
    (net (code "62") (name "Net-(U14A-IN-)") (class "Default")
      (node (ref "R80") (pin "1") (pinfunction "1_1") (pintype "passive"))
      (node (ref "U14") (pin "1") (pinfunction "OUT_1") (pintype "passive"))
      (node (ref "U14") (pin "4") (pinfunction "IN-_4") (pintype "passive"))
    )
    (net (code "63") (name "unconnected-(JX3-N{slash}A-Pad2)") (class "Default")
      (node (ref "JX3") (pin "2") (pinfunction "N/A_2") (pintype "passive+no_connect"))
    )
    (net (code "64") (name "unconnected-(JX3-N{slash}A-Pad3)") (class "Default")
      (node (ref "JX3") (pin "3") (pinfunction "N/A_3") (pintype "passive+no_connect"))
    )
    (net (code "65") (name "unconnected-(JX3-N{slash}A-Pad5)") (class "Default")
      (node (ref "JX3") (pin "5") (pinfunction "N/A_5") (pintype "passive+no_connect"))
    )
    (net (code "66") (name "unconnected-(JX3-N{slash}A-Pad6)") (class "Default")
      (node (ref "JX3") (pin "6") (pinfunction "N/A_6") (pintype "passive+no_connect"))
    )
    (net (code "67") (name "unconnected-(JX3-N{slash}A-Pad7)") (class "Default")
      (node (ref "JX3") (pin "7") (pinfunction "N/A_7") (pintype "passive+no_connect"))
    )
    (net (code "68") (name "unconnected-(JX3-N{slash}A-Pad8)") (class "Default")
      (node (ref "JX3") (pin "8") (pinfunction "N/A_8") (pintype "passive+no_connect"))
    )
    (net (code "69") (name "unconnected-(JX3-N{slash}A-Pad53)") (class "Default")
      (node (ref "JX3") (pin "53") (pinfunction "N/A_53") (pintype "passive+no_connect"))
    )
    (net (code "70") (name "unconnected-(JX3-N{slash}A-Pad54)") (class "Default")
      (node (ref "JX3") (pin "54") (pinfunction "N/A_54") (pintype "passive+no_connect"))
    )
    (net (code "71") (name "unconnected-(JX3-N{slash}A-Pad55)") (class "Default")
      (node (ref "JX3") (pin "55") (pinfunction "N/A_55") (pintype "passive+no_connect"))
    )
    (net (code "72") (name "unconnected-(JX3-N{slash}A-Pad56)") (class "Default")
      (node (ref "JX3") (pin "56") (pinfunction "N/A_56") (pintype "passive+no_connect"))
    )
    (net (code "73") (name "unconnected-(JX3-N{slash}A-Pad58)") (class "Default")
      (node (ref "JX3") (pin "58") (pinfunction "N/A_58") (pintype "passive+no_connect"))
    )
    (net (code "74") (name "unconnected-(JX3-N{slash}A-Pad59)") (class "Default")
      (node (ref "JX3") (pin "59") (pinfunction "N/A_59") (pintype "passive+no_connect"))
    )
    (net (code "75") (name "unconnected-(LAN1-NC_1-Pad4)") (class "Default")
      (node (ref "LAN1") (pin "4") (pinfunction "NC_1_4") (pintype "passive"))
    )
    (net (code "76") (name "unconnected-(LAN1-NC_2-Pad5)") (class "Default")
      (node (ref "LAN1") (pin "5") (pinfunction "NC_2_5") (pintype "passive"))
    )
    (net (code "77") (name "unconnected-(LAN1-NC_3-Pad12)") (class "Default")
      (node (ref "LAN1") (pin "12") (pinfunction "NC_3_12") (pintype "passive"))
    )
    (net (code "78") (name "unconnected-(LAN1-NC_4-Pad13)") (class "Default")
      (node (ref "LAN1") (pin "13") (pinfunction "NC_4_13") (pintype "passive"))
    )
    (net (code "79") (name "unconnected-(LAN1-RD+-Pad6)") (class "Default")
      (node (ref "LAN1") (pin "6") (pinfunction "RD+_6") (pintype "passive"))
    )
    (net (code "80") (name "unconnected-(LAN1-RD--Pad8)") (class "Default")
      (node (ref "LAN1") (pin "8") (pinfunction "RD-_8") (pintype "passive"))
    )
    (net (code "81") (name "unconnected-(LAN1-RDCT-Pad7)") (class "Default")
      (node (ref "LAN1") (pin "7") (pinfunction "RDCT_7") (pintype "passive"))
    )
    (net (code "82") (name "unconnected-(LAN1-TD+-Pad1)") (class "Default")
      (node (ref "LAN1") (pin "1") (pinfunction "TD+_1") (pintype "passive"))
    )
    (net (code "83") (name "unconnected-(LAN1-TD--Pad3)") (class "Default")
      (node (ref "LAN1") (pin "3") (pinfunction "TD-_3") (pintype "passive"))
    )
    (net (code "84") (name "unconnected-(LAN1-TDCT-Pad2)") (class "Default")
      (node (ref "LAN1") (pin "2") (pinfunction "TDCT_2") (pintype "passive"))
    )
  )
)
